# QSPI.net
KiCad netlist of a schematic drawn in Altium Designer
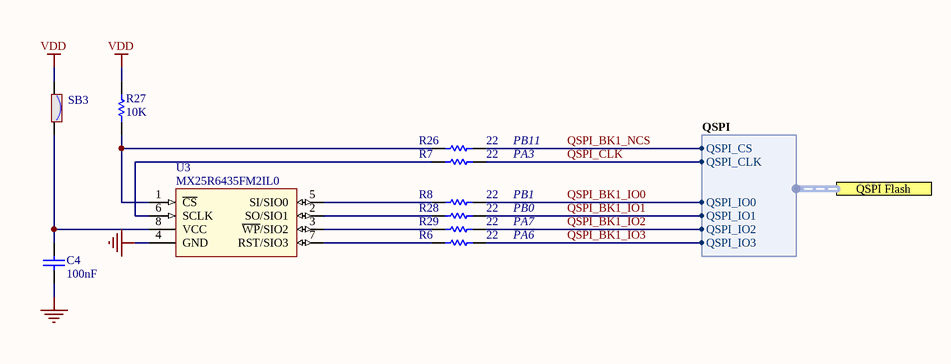
[diagram p0: QSPI.SchDoc]

(export (version "E")
  (design (tool "Eeschema 10.0.6"))
  (components
    (comp (ref "C4")
      (value "100nF")
      (footprint "0603C")
      (description "Capacitor,100nF,10%,16V,X7R,0603,YAGEO")
      (fields (field (name "Comment") "CC0603KRX7R7BB104") (field (name "PUBLISHER") "Altium Limited"))
      (libsource (lib "Miscellaneous Devices") (part "Cap"))
    )
    (comp (ref "R6")
      (value "22")
      (footprint "0603R")
      (description "Resistor, 22 ,0603,1%,YAGEO")
      (fields (field (name "Comment") "RC0603JR-0722RL") (field (name "PUBLISHER") "Altium Limited"))
      (libsource (lib "Miscellaneous Devices") (part "res1"))
    )
    (comp (ref "R7")
      (value "22")
      (footprint "0603R")
      (description "Resistor, 22 ,0603,1%,YAGEO")
      (fields (field (name "Comment") "RC0603JR-0722RL") (field (name "PUBLISHER") "Altium Limited"))
      (libsource (lib "Miscellaneous Devices") (part "res1"))
    )
    (comp (ref "R8")
      (value "22")
      (footprint "0603R")
      (description "Resistor, 22 ,0603,1%,YAGEO")
      (fields (field (name "Comment") "RC0603JR-0722RL") (field (name "PUBLISHER") "Altium Limited"))
      (libsource (lib "Miscellaneous Devices") (part "res1"))
    )
    (comp (ref "R26")
      (value "22")
      (footprint "0603R")
      (description "Resistor, 22 ,0603,1%,YAGEO")
      (fields (field (name "Comment") "RC0603JR-0722RL") (field (name "PUBLISHER") "Altium Limited"))
      (libsource (lib "Miscellaneous Devices") (part "res1"))
    )
    (comp (ref "R27")
      (value "10K")
      (footprint "0603R")
      (description "Resistor,10K,0603,1%,YAGEO")
      (fields (field (name "Comment") "RC0603FR-0710KL") (field (name "PUBLISHER") "Altium Limited"))
      (libsource (lib "Miscellaneous Devices") (part "res1"))
    )
    (comp (ref "R28")
      (value "22")
      (footprint "0603R")
      (description "Resistor, 22 ,0603,1%,YAGEO")
      (fields (field (name "Comment") "RC0603JR-0722RL") (field (name "PUBLISHER") "Altium Limited"))
      (libsource (lib "Miscellaneous Devices") (part "res1"))
    )
    (comp (ref "R29")
      (value "22")
      (footprint "0603R")
      (description "Resistor, 22 ,0603,1%,YAGEO")
      (fields (field (name "Comment") "RC0603JR-0722RL") (field (name "PUBLISHER") "Altium Limited"))
      (libsource (lib "Miscellaneous Devices") (part "res1"))
    )
    (comp (ref "SB3")
      (value "Solder Bridge ON")
      (footprint "SB_0603")
      (libsource (lib "MCD_TOOLS") (part "SB_ON"))
    )
    (comp (ref "U3")
      (value "MX25R6435FM2IL0")
      (footprint "SOIC8_1R27_5R28X7R9")
      (description "Ultra Low Power 64M-BIT CMOS MXSMIO FLASH MEMORY")
      (libsource (lib "Big Orga") (part "MX25R6435FM2IL0"))
    )
  )
  (nets
    (net (code "2") (name "/QSPI_BK1_IO0") (class "Default")
      (node (ref "R8") (pin "1") (pinfunction "1_1") (pintype "passive"))
    )
    (net (code "3") (name "/QSPI_BK1_IO1") (class "Default")
      (node (ref "R28") (pin "1") (pinfunction "1_1") (pintype "passive"))
    )
    (net (code "4") (name "/QSPI_BK1_IO2") (class "Default")
      (node (ref "R29") (pin "1") (pinfunction "1_1") (pintype "passive"))
    )
    (net (code "5") (name "/QSPI_BK1_IO3") (class "Default")
      (node (ref "R6") (pin "1") (pinfunction "1_1") (pintype "passive"))
    )
    (net (code "6") (name "/QSPI_BK1_NCS") (class "Default")
      (node (ref "R26") (pin "1") (pinfunction "1_1") (pintype "passive"))
    )
    (net (code "7") (name "/QSPI_CLK") (class "Default")
      (node (ref "R7") (pin "1") (pinfunction "1_1") (pintype "passive"))
    )
    (net (code "9") (name "GND") (class "Default")
      (node (ref "C4") (pin "2") (pinfunction "2_2") (pintype "passive"))
      (node (ref "U3") (pin "4") (pinfunction "GND_4") (pintype "power_in"))
    )
    (net (code "10") (name "Net-(U3-RST{slash}SIO3)") (class "Default")
      (node (ref "R6") (pin "2") (pinfunction "2_2") (pintype "passive"))
      (node (ref "U3") (pin "7") (pinfunction "RST/SIO3_7") (pintype "bidirectional"))
    )
    (net (code "11") (name "Net-(U3-SCLK)") (class "Default")
      (node (ref "R7") (pin "2") (pinfunction "2_2") (pintype "passive"))
      (node (ref "U3") (pin "6") (pinfunction "SCLK_6") (pintype "input"))
    )
    (net (code "12") (name "Net-(U3-SI{slash}SIO0)") (class "Default")
      (node (ref "R8") (pin "2") (pinfunction "2_2") (pintype "passive"))
      (node (ref "U3") (pin "5") (pinfunction "SI/SIO0_5") (pintype "bidirectional"))
    )
    (net (code "13") (name "Net-(U3-SO{slash}SIO1)") (class "Default")
      (node (ref "R28") (pin "2") (pinfunction "2_2") (pintype "passive"))
      (node (ref "U3") (pin "2") (pinfunction "SO/SIO1_2") (pintype "bidirectional"))
    )
    (net (code "14") (name "Net-(U3-VCC)") (class "Default")
      (node (ref "C4") (pin "1") (pinfunction "1_1") (pintype "passive"))
      (node (ref "SB3") (pin "2") (pinfunction "2_2") (pintype "passive"))
      (node (ref "U3") (pin "8") (pinfunction "VCC_8") (pintype "passive"))
    )
    (net (code "15") (name "Net-(U3-~{CS})") (class "Default")
      (node (ref "R26") (pin "2") (pinfunction "2_2") (pintype "passive"))
      (node (ref "R27") (pin "1") (pinfunction "1_1") (pintype "passive"))
      (node (ref "U3") (pin "1") (pinfunction "~{CS}_1") (pintype "input"))
    )
    (net (code "16") (name "Net-(U3-~{WP}{slash}SIO2)") (class "Default")
      (node (ref "R29") (pin "2") (pinfunction "2_2") (pintype "passive"))
      (node (ref "U3") (pin "3") (pinfunction "~{WP}/SIO2_3") (pintype "bidirectional"))
    )
    (net (code "17") (name "VDD") (class "Default")
      (node (ref "R27") (pin "2") (pinfunction "2_2") (pintype "passive"))
      (node (ref "SB3") (pin "1") (pinfunction "1_1") (pintype "passive"))
    )
  )
)
